# IN_OUT.net
KiCad netlist of a schematic drawn in Altium Designer
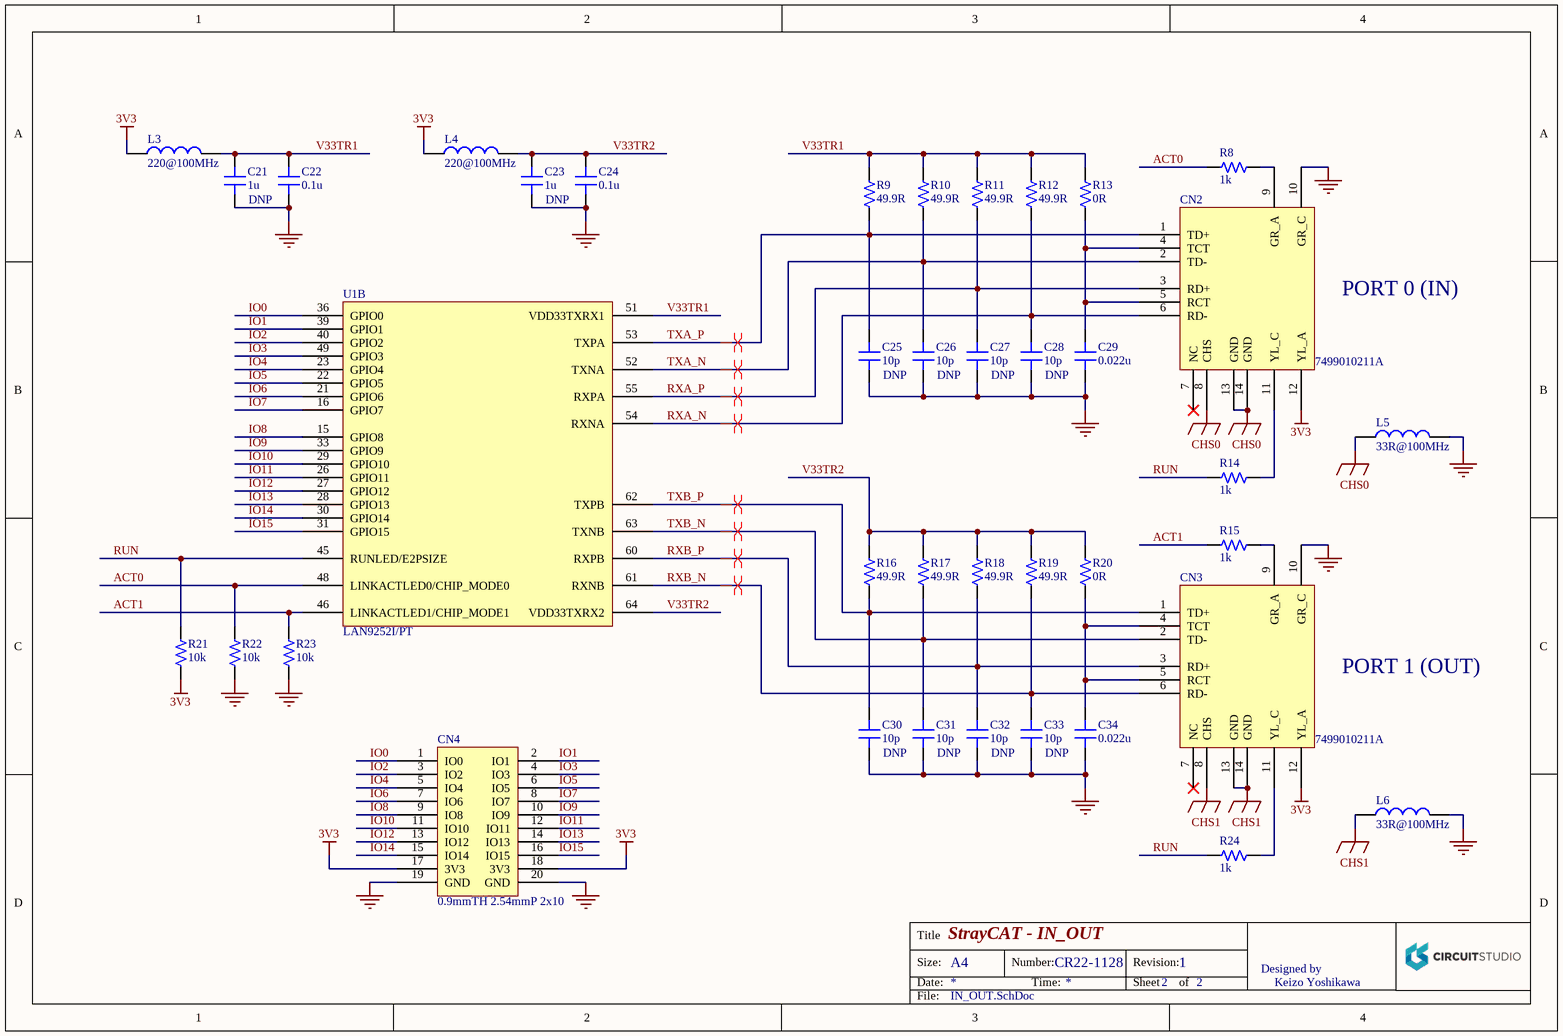
[diagram p0: IN_OUT.SchDoc]

(export (version "E")
  (design (tool "Eeschema 10.0.6"))
  (components
    (comp (ref "C21")
      (value "1u")
      (footprint "CGA3")
      (description "1608 1uF 25V X7R 10%")
      (libsource (lib "CGA3") (part "CGA3E1X7R1E105K080AC"))
    )
    (comp (ref "C22")
      (value "0.1u")
      (footprint "CGA3")
      (description "1608 0.1uF 50V X7R 10%")
      (libsource (lib "CGA3") (part "CGA3E2X7R1H104K080AA"))
    )
    (comp (ref "C23")
      (value "1u")
      (footprint "CGA3")
      (description "1608 1uF 25V X7R 10%")
      (libsource (lib "CGA3") (part "CGA3E1X7R1E105K080AC"))
    )
    (comp (ref "C24")
      (value "0.1u")
      (footprint "CGA3")
      (description "1608 0.1uF 50V X7R 10%")
      (libsource (lib "CGA3") (part "CGA3E2X7R1H104K080AA"))
    )
    (comp (ref "C25")
      (value "10p")
      (footprint "CGA3")
      (description "1608 10pF 50V C0G 5%")
      (libsource (lib "CGA3") (part "CGA3E2C0G1H100D080AA"))
    )
    (comp (ref "C26")
      (value "10p")
      (footprint "CGA3")
      (description "1608 10pF 50V C0G 5%")
      (libsource (lib "CGA3") (part "CGA3E2C0G1H100D080AA"))
    )
    (comp (ref "C27")
      (value "10p")
      (footprint "CGA3")
      (description "1608 10pF 50V C0G 5%")
      (libsource (lib "CGA3") (part "CGA3E2C0G1H100D080AA"))
    )
    (comp (ref "C28")
      (value "10p")
      (footprint "CGA3")
      (description "1608 10pF 50V C0G 5%")
      (libsource (lib "CGA3") (part "CGA3E2C0G1H100D080AA"))
    )
    (comp (ref "C29")
      (value "0.022u")
      (footprint "CGA3")
      (description "1608 0.022uF 50V X7R 10%")
      (libsource (lib "CGA3") (part "CGA3E2X7R1H223K080AA"))
    )
    (comp (ref "C30")
      (value "10p")
      (footprint "CGA3")
      (description "1608 10pF 50V C0G 5%")
      (libsource (lib "CGA3") (part "CGA3E2C0G1H100D080AA"))
    )
    (comp (ref "C31")
      (value "10p")
      (footprint "CGA3")
      (description "1608 10pF 50V C0G 5%")
      (libsource (lib "CGA3") (part "CGA3E2C0G1H100D080AA"))
    )
    (comp (ref "C32")
      (value "10p")
      (footprint "CGA3")
      (description "1608 10pF 50V C0G 5%")
      (libsource (lib "CGA3") (part "CGA3E2C0G1H100D080AA"))
    )
    (comp (ref "C33")
      (value "10p")
      (footprint "CGA3")
      (description "1608 10pF 50V C0G 5%")
      (libsource (lib "CGA3") (part "CGA3E2C0G1H100D080AA"))
    )
    (comp (ref "C34")
      (value "0.022u")
      (footprint "CGA3")
      (description "1608 0.022uF 50V X7R 10%")
      (libsource (lib "CGA3") (part "CGA3E2X7R1H223K080AA"))
    )
    (comp (ref "CN2")
      (value "7499010211A")
      (footprint "7499010211A")
      (description "WE-RJ45LAN 10/100 Base-T")
      (libsource (lib "7499010211A") (part "7499010211A"))
    )
    (comp (ref "CN3")
      (value "7499010211A")
      (footprint "7499010211A")
      (description "WE-RJ45LAN 10/100 Base-T")
      (libsource (lib "7499010211A") (part "7499010211A"))
    )
    (comp (ref "CN4")
      (value "0.9mmTH 2.54mmP 2x10")
      (footprint "61302021121")
      (description "WR-PHD Pin Header 20pin")
      (libsource (lib "61302021121") (part "61302021121"))
    )
    (comp (ref "L3")
      (value "220@100MHz")
      (footprint "BLM18EG221SN1D")
      (description "Noise Suppression Chip Ferrite Bead")
      (libsource (lib "BLM18EG221SN1D") (part "BLM18EG221SN1D"))
    )
    (comp (ref "L4")
      (value "220@100MHz")
      (footprint "BLM18EG221SN1D")
      (description "Noise Suppression Chip Ferrite Bead")
      (libsource (lib "BLM18EG221SN1D") (part "BLM18EG221SN1D"))
    )
    (comp (ref "L5")
      (value "33R@100MHz")
      (footprint "BLM18PG330SN1D")
      (description "Noise Suppression Chip Ferrite Bead")
      (libsource (lib "BLM18PG330SN1D") (part "BLM18PG330SN1D"))
    )
    (comp (ref "L6")
      (value "33R@100MHz")
      (footprint "BLM18PG330SN1D")
      (description "Noise Suppression Chip Ferrite Bead")
      (libsource (lib "BLM18PG330SN1D") (part "BLM18PG330SN1D"))
    )
    (comp (ref "R8")
      (value "1k")
      (footprint "RK73x1J")
      (description "1608 1kOhm 5% 1/8W")
      (libsource (lib "RK73X1J") (part "RK73B1JTTD102J"))
    )
    (comp (ref "R9")
      (value "49.9R")
      (footprint "RK73x1J")
      (description "1608 49.9Ohm 1% 1/8W")
      (libsource (lib "RK73X1J") (part "RK73H1JTTD49R9F"))
    )
    (comp (ref "R10")
      (value "49.9R")
      (footprint "RK73x1J")
      (description "1608 49.9Ohm 1% 1/8W")
      (libsource (lib "RK73X1J") (part "RK73H1JTTD49R9F"))
    )
    (comp (ref "R11")
      (value "49.9R")
      (footprint "RK73x1J")
      (description "1608 49.9Ohm 1% 1/8W")
      (libsource (lib "RK73X1J") (part "RK73H1JTTD49R9F"))
    )
    (comp (ref "R12")
      (value "49.9R")
      (footprint "RK73x1J")
      (description "1608 49.9Ohm 1% 1/8W")
      (libsource (lib "RK73X1J") (part "RK73H1JTTD49R9F"))
    )
    (comp (ref "R13")
      (value "0R")
      (footprint "RK73x1J")
      (description "1608 0-Ohm 1A")
      (libsource (lib "RK73X1J") (part "RK73Z1JTTD"))
    )
    (comp (ref "R14")
      (value "1k")
      (footprint "RK73x1J")
      (description "1608 1kOhm 5% 1/8W")
      (libsource (lib "RK73X1J") (part "RK73B1JTTD102J"))
    )
    (comp (ref "R15")
      (value "1k")
      (footprint "RK73x1J")
      (description "1608 1kOhm 5% 1/8W")
      (libsource (lib "RK73X1J") (part "RK73B1JTTD102J"))
    )
    (comp (ref "R16")
      (value "49.9R")
      (footprint "RK73x1J")
      (description "1608 49.9Ohm 1% 1/8W")
      (libsource (lib "RK73X1J") (part "RK73H1JTTD49R9F"))
    )
    (comp (ref "R17")
      (value "49.9R")
      (footprint "RK73x1J")
      (description "1608 49.9Ohm 1% 1/8W")
      (libsource (lib "RK73X1J") (part "RK73H1JTTD49R9F"))
    )
    (comp (ref "R18")
      (value "49.9R")
      (footprint "RK73x1J")
      (description "1608 49.9Ohm 1% 1/8W")
      (libsource (lib "RK73X1J") (part "RK73H1JTTD49R9F"))
    )
    (comp (ref "R19")
      (value "49.9R")
      (footprint "RK73x1J")
      (description "1608 49.9Ohm 1% 1/8W")
      (libsource (lib "RK73X1J") (part "RK73H1JTTD49R9F"))
    )
    (comp (ref "R20")
      (value "0R")
      (footprint "RK73x1J")
      (description "1608 0-Ohm 1A")
      (libsource (lib "RK73X1J") (part "RK73Z1JTTD"))
    )
    (comp (ref "R21")
      (value "10k")
      (footprint "RK73x1J")
      (description "1608 10kOhm 5% 1/10W")
      (libsource (lib "RK73X1J") (part "RK73B1JTTD103J"))
    )
    (comp (ref "R22")
      (value "10k")
      (footprint "RK73x1J")
      (description "1608 10kOhm 5% 1/10W")
      (libsource (lib "RK73X1J") (part "RK73B1JTTD103J"))
    )
    (comp (ref "R23")
      (value "10k")
      (footprint "RK73x1J")
      (description "1608 10kOhm 5% 1/10W")
      (libsource (lib "RK73X1J") (part "RK73B1JTTD103J"))
    )
    (comp (ref "R24")
      (value "1k")
      (footprint "RK73x1J")
      (description "1608 1kOhm 5% 1/8W")
      (libsource (lib "RK73X1J") (part "RK73B1JTTD102J"))
    )
    (comp (ref "U1")
      (value "LAN9252I/PT")
      (footprint "TSQFP50P1200X1200X105_HS-65N")
      (description "EtherCAT Slave Controller")
      (libsource (lib "LAN9252I_PT") (part "LAN9252I_PT"))
    )
  )
  (nets
    (net (code "1") (name "/ACT0") (class "Default")
      (node (ref "R22") (pin "1") (pinfunction "1_1") (pintype "passive"))
      (node (ref "R8") (pin "1") (pinfunction "1_1") (pintype "passive"))
      (node (ref "U1") (pin "48") (pinfunction "LINKACTLED0/CHIP_MODE0_48") (pintype "passive"))
    )
    (net (code "2") (name "/ACT1") (class "Default")
      (node (ref "R15") (pin "1") (pinfunction "1_1") (pintype "passive"))
      (node (ref "R23") (pin "1") (pinfunction "1_1") (pintype "passive"))
      (node (ref "U1") (pin "46") (pinfunction "LINKACTLED1/CHIP_MODE1_46") (pintype "passive"))
    )
    (net (code "3") (name "/IO0") (class "Default")
      (node (ref "CN4") (pin "1") (pinfunction "IO0_1") (pintype "passive"))
      (node (ref "U1") (pin "36") (pinfunction "GPIO0_36") (pintype "passive"))
    )
    (net (code "4") (name "/IO1") (class "Default")
      (node (ref "CN4") (pin "2") (pinfunction "IO1_2") (pintype "passive"))
      (node (ref "U1") (pin "39") (pinfunction "GPIO1_39") (pintype "passive"))
    )
    (net (code "5") (name "/IO2") (class "Default")
      (node (ref "CN4") (pin "3") (pinfunction "IO2_3") (pintype "passive"))
      (node (ref "U1") (pin "40") (pinfunction "GPIO2_40") (pintype "passive"))
    )
    (net (code "6") (name "/IO3") (class "Default")
      (node (ref "CN4") (pin "4") (pinfunction "IO3_4") (pintype "passive"))
      (node (ref "U1") (pin "49") (pinfunction "GPIO3_49") (pintype "passive"))
    )
    (net (code "7") (name "/IO4") (class "Default")
      (node (ref "CN4") (pin "5") (pinfunction "IO4_5") (pintype "passive"))
      (node (ref "U1") (pin "23") (pinfunction "GPIO4_23") (pintype "passive"))
    )
    (net (code "8") (name "/IO5") (class "Default")
      (node (ref "CN4") (pin "6") (pinfunction "IO5_6") (pintype "passive"))
      (node (ref "U1") (pin "22") (pinfunction "GPIO5_22") (pintype "passive"))
    )
    (net (code "9") (name "/IO6") (class "Default")
      (node (ref "CN4") (pin "7") (pinfunction "IO6_7") (pintype "passive"))
      (node (ref "U1") (pin "21") (pinfunction "GPIO6_21") (pintype "passive"))
    )
    (net (code "10") (name "/IO7") (class "Default")
      (node (ref "CN4") (pin "8") (pinfunction "IO7_8") (pintype "passive"))
      (node (ref "U1") (pin "16") (pinfunction "GPIO7_16") (pintype "passive"))
    )
    (net (code "11") (name "/IO8") (class "Default")
      (node (ref "CN4") (pin "9") (pinfunction "IO8_9") (pintype "passive"))
      (node (ref "U1") (pin "15") (pinfunction "GPIO8_15") (pintype "passive"))
    )
    (net (code "12") (name "/IO9") (class "Default")
      (node (ref "CN4") (pin "10") (pinfunction "IO9_10") (pintype "passive"))
      (node (ref "U1") (pin "33") (pinfunction "GPIO9_33") (pintype "passive"))
    )
    (net (code "13") (name "/IO10") (class "Default")
      (node (ref "CN4") (pin "11") (pinfunction "IO10_11") (pintype "passive"))
      (node (ref "U1") (pin "29") (pinfunction "GPIO10_29") (pintype "passive"))
    )
    (net (code "14") (name "/IO11") (class "Default")
      (node (ref "CN4") (pin "12") (pinfunction "IO11_12") (pintype "passive"))
      (node (ref "U1") (pin "26") (pinfunction "GPIO11_26") (pintype "passive"))
    )
    (net (code "15") (name "/IO12") (class "Default")
      (node (ref "CN4") (pin "13") (pinfunction "IO12_13") (pintype "passive"))
      (node (ref "U1") (pin "27") (pinfunction "GPIO12_27") (pintype "passive"))
    )
    (net (code "16") (name "/IO13") (class "Default")
      (node (ref "CN4") (pin "14") (pinfunction "IO13_14") (pintype "passive"))
      (node (ref "U1") (pin "28") (pinfunction "GPIO13_28") (pintype "passive"))
    )
    (net (code "17") (name "/IO14") (class "Default")
      (node (ref "CN4") (pin "15") (pinfunction "IO14_15") (pintype "passive"))
      (node (ref "U1") (pin "30") (pinfunction "GPIO14_30") (pintype "passive"))
    )
    (net (code "18") (name "/IO15") (class "Default")
      (node (ref "CN4") (pin "16") (pinfunction "IO15_16") (pintype "passive"))
      (node (ref "U1") (pin "31") (pinfunction "GPIO15_31") (pintype "passive"))
    )
    (net (code "19") (name "/RUN") (class "Default")
      (node (ref "R14") (pin "1") (pinfunction "1_1") (pintype "passive"))
      (node (ref "R21") (pin "1") (pinfunction "1_1") (pintype "passive"))
      (node (ref "R24") (pin "1") (pinfunction "1_1") (pintype "passive"))
      (node (ref "U1") (pin "45") (pinfunction "RUNLED/E2PSIZE_45") (pintype "passive"))
    )
    (net (code "20") (name "/RXA_N") (class "Default")
      (node (ref "C28") (pin "1") (pinfunction "1_1") (pintype "passive"))
      (node (ref "CN2") (pin "6") (pinfunction "RD-_6") (pintype "passive"))
      (node (ref "R12") (pin "2") (pinfunction "2_2") (pintype "passive"))
      (node (ref "U1") (pin "54") (pinfunction "RXNA_54") (pintype "passive"))
    )
    (net (code "21") (name "/RXA_P") (class "Default")
      (node (ref "C27") (pin "1") (pinfunction "1_1") (pintype "passive"))
      (node (ref "CN2") (pin "3") (pinfunction "RD+_3") (pintype "passive"))
      (node (ref "R11") (pin "2") (pinfunction "2_2") (pintype "passive"))
      (node (ref "U1") (pin "55") (pinfunction "RXPA_55") (pintype "passive"))
    )
    (net (code "22") (name "/RXB_N") (class "Default")
      (node (ref "C33") (pin "1") (pinfunction "1_1") (pintype "passive"))
      (node (ref "CN3") (pin "6") (pinfunction "RD-_6") (pintype "passive"))
      (node (ref "R19") (pin "2") (pinfunction "2_2") (pintype "passive"))
      (node (ref "U1") (pin "61") (pinfunction "RXNB_61") (pintype "passive"))
    )
    (net (code "23") (name "/RXB_P") (class "Default")
      (node (ref "C32") (pin "1") (pinfunction "1_1") (pintype "passive"))
      (node (ref "CN3") (pin "3") (pinfunction "RD+_3") (pintype "passive"))
      (node (ref "R18") (pin "2") (pinfunction "2_2") (pintype "passive"))
      (node (ref "U1") (pin "60") (pinfunction "RXPB_60") (pintype "passive"))
    )
    (net (code "24") (name "/TXA_N") (class "Default")
      (node (ref "C26") (pin "1") (pinfunction "1_1") (pintype "passive"))
      (node (ref "CN2") (pin "2") (pinfunction "TD-_2") (pintype "passive"))
      (node (ref "R10") (pin "2") (pinfunction "2_2") (pintype "passive"))
      (node (ref "U1") (pin "52") (pinfunction "TXNA_52") (pintype "passive"))
    )
    (net (code "25") (name "/TXA_P") (class "Default")
      (node (ref "C25") (pin "1") (pinfunction "1_1") (pintype "passive"))
      (node (ref "CN2") (pin "1") (pinfunction "TD+_1") (pintype "passive"))
      (node (ref "R9") (pin "2") (pinfunction "2_2") (pintype "passive"))
      (node (ref "U1") (pin "53") (pinfunction "TXPA_53") (pintype "passive"))
    )
    (net (code "26") (name "/TXB_N") (class "Default")
      (node (ref "C31") (pin "1") (pinfunction "1_1") (pintype "passive"))
      (node (ref "CN3") (pin "2") (pinfunction "TD-_2") (pintype "passive"))
      (node (ref "R17") (pin "2") (pinfunction "2_2") (pintype "passive"))
      (node (ref "U1") (pin "63") (pinfunction "TXNB_63") (pintype "passive"))
    )
    (net (code "27") (name "/TXB_P") (class "Default")
      (node (ref "C30") (pin "1") (pinfunction "1_1") (pintype "passive"))
      (node (ref "CN3") (pin "1") (pinfunction "TD+_1") (pintype "passive"))
      (node (ref "R16") (pin "2") (pinfunction "2_2") (pintype "passive"))
      (node (ref "U1") (pin "62") (pinfunction "TXPB_62") (pintype "passive"))
    )
    (net (code "28") (name "/V33TR1") (class "Default")
      (node (ref "C21") (pin "1") (pinfunction "1_1") (pintype "passive"))
      (node (ref "C22") (pin "1") (pinfunction "1_1") (pintype "passive"))
      (node (ref "L3") (pin "2") (pinfunction "2_2") (pintype "passive"))
      (node (ref "R10") (pin "1") (pinfunction "1_1") (pintype "passive"))
      (node (ref "R11") (pin "1") (pinfunction "1_1") (pintype "passive"))
      (node (ref "R12") (pin "1") (pinfunction "1_1") (pintype "passive"))
      (node (ref "R13") (pin "1") (pinfunction "1_1") (pintype "passive"))
      (node (ref "R9") (pin "1") (pinfunction "1_1") (pintype "passive"))
      (node (ref "U1") (pin "51") (pinfunction "VDD33TXRX1_51") (pintype "passive"))
    )
    (net (code "29") (name "/V33TR2") (class "Default")
      (node (ref "C23") (pin "1") (pinfunction "1_1") (pintype "passive"))
      (node (ref "C24") (pin "1") (pinfunction "1_1") (pintype "passive"))
      (node (ref "L4") (pin "2") (pinfunction "2_2") (pintype "passive"))
      (node (ref "R16") (pin "1") (pinfunction "1_1") (pintype "passive"))
      (node (ref "R17") (pin "1") (pinfunction "1_1") (pintype "passive"))
      (node (ref "R18") (pin "1") (pinfunction "1_1") (pintype "passive"))
      (node (ref "R19") (pin "1") (pinfunction "1_1") (pintype "passive"))
      (node (ref "R20") (pin "1") (pinfunction "1_1") (pintype "passive"))
      (node (ref "U1") (pin "64") (pinfunction "VDD33TXRX2_64") (pintype "passive"))
    )
    (net (code "30") (name "3V3") (class "Default")
      (node (ref "CN2") (pin "12") (pinfunction "YL_A_12") (pintype "passive"))
      (node (ref "CN3") (pin "12") (pinfunction "YL_A_12") (pintype "passive"))
      (node (ref "CN4") (pin "17") (pinfunction "3V3_17") (pintype "passive"))
      (node (ref "CN4") (pin "18") (pinfunction "3V3_18") (pintype "passive"))
      (node (ref "L3") (pin "1") (pinfunction "1_1") (pintype "passive"))
      (node (ref "L4") (pin "1") (pinfunction "1_1") (pintype "passive"))
      (node (ref "R21") (pin "2") (pinfunction "2_2") (pintype "passive"))
    )
    (net (code "31") (name "CHS0") (class "Default")
      (node (ref "CN2") (pin "13") (pinfunction "GND_13") (pintype "passive"))
      (node (ref "CN2") (pin "14") (pinfunction "GND_14") (pintype "passive"))
      (node (ref "CN2") (pin "8") (pinfunction "CHS_8") (pintype "passive"))
      (node (ref "L5") (pin "1") (pinfunction "1_1") (pintype "passive"))
    )
    (net (code "32") (name "CHS1") (class "Default")
      (node (ref "CN3") (pin "13") (pinfunction "GND_13") (pintype "passive"))
      (node (ref "CN3") (pin "14") (pinfunction "GND_14") (pintype "passive"))
      (node (ref "CN3") (pin "8") (pinfunction "CHS_8") (pintype "passive"))
      (node (ref "L6") (pin "1") (pinfunction "1_1") (pintype "passive"))
    )
    (net (code "33") (name "GND") (class "Default")
      (node (ref "C21") (pin "2") (pinfunction "2_2") (pintype "passive"))
      (node (ref "C22") (pin "2") (pinfunction "2_2") (pintype "passive"))
      (node (ref "C23") (pin "2") (pinfunction "2_2") (pintype "passive"))
      (node (ref "C24") (pin "2") (pinfunction "2_2") (pintype "passive"))
      (node (ref "C25") (pin "2") (pinfunction "2_2") (pintype "passive"))
      (node (ref "C26") (pin "2") (pinfunction "2_2") (pintype "passive"))
      (node (ref "C27") (pin "2") (pinfunction "2_2") (pintype "passive"))
      (node (ref "C28") (pin "2") (pinfunction "2_2") (pintype "passive"))
      (node (ref "C29") (pin "2") (pinfunction "2_2") (pintype "passive"))
      (node (ref "C30") (pin "2") (pinfunction "2_2") (pintype "passive"))
      (node (ref "C31") (pin "2") (pinfunction "2_2") (pintype "passive"))
      (node (ref "C32") (pin "2") (pinfunction "2_2") (pintype "passive"))
      (node (ref "C33") (pin "2") (pinfunction "2_2") (pintype "passive"))
      (node (ref "C34") (pin "2") (pinfunction "2_2") (pintype "passive"))
      (node (ref "CN2") (pin "10") (pinfunction "GR_C_10") (pintype "passive"))
      (node (ref "CN3") (pin "10") (pinfunction "GR_C_10") (pintype "passive"))
      (node (ref "CN4") (pin "19") (pinfunction "GND_19") (pintype "passive"))
      (node (ref "CN4") (pin "20") (pinfunction "GND_20") (pintype "passive"))
      (node (ref "L5") (pin "2") (pinfunction "2_2") (pintype "passive"))
      (node (ref "L6") (pin "2") (pinfunction "2_2") (pintype "passive"))
      (node (ref "R22") (pin "2") (pinfunction "2_2") (pintype "passive"))
      (node (ref "R23") (pin "2") (pinfunction "2_2") (pintype "passive"))
    )
    (net (code "34") (name "Net-(CN2-GR_A)") (class "Default")
      (node (ref "CN2") (pin "9") (pinfunction "GR_A_9") (pintype "passive"))
      (node (ref "R8") (pin "2") (pinfunction "2_2") (pintype "passive"))
    )
    (net (code "35") (name "Net-(CN2-RCT)") (class "Default")
      (node (ref "C29") (pin "1") (pinfunction "1_1") (pintype "passive"))
      (node (ref "CN2") (pin "4") (pinfunction "TCT_4") (pintype "passive"))
      (node (ref "CN2") (pin "5") (pinfunction "RCT_5") (pintype "passive"))
      (node (ref "R13") (pin "2") (pinfunction "2_2") (pintype "passive"))
    )
    (net (code "36") (name "Net-(CN2-YL_C)") (class "Default")
      (node (ref "CN2") (pin "11") (pinfunction "YL_C_11") (pintype "passive"))
      (node (ref "R14") (pin "2") (pinfunction "2_2") (pintype "passive"))
    )
    (net (code "37") (name "Net-(CN3-GR_A)") (class "Default")
      (node (ref "CN3") (pin "9") (pinfunction "GR_A_9") (pintype "passive"))
      (node (ref "R15") (pin "2") (pinfunction "2_2") (pintype "passive"))
    )
    (net (code "38") (name "Net-(CN3-RCT)") (class "Default")
      (node (ref "C34") (pin "1") (pinfunction "1_1") (pintype "passive"))
      (node (ref "CN3") (pin "4") (pinfunction "TCT_4") (pintype "passive"))
      (node (ref "CN3") (pin "5") (pinfunction "RCT_5") (pintype "passive"))
      (node (ref "R20") (pin "2") (pinfunction "2_2") (pintype "passive"))
    )
    (net (code "39") (name "Net-(CN3-YL_C)") (class "Default")
      (node (ref "CN3") (pin "11") (pinfunction "YL_C_11") (pintype "passive"))
      (node (ref "R24") (pin "2") (pinfunction "2_2") (pintype "passive"))
    )
    (net (code "40") (name "unconnected-(CN2-NC-Pad7)") (class "Default")
      (node (ref "CN2") (pin "7") (pinfunction "NC_7") (pintype "passive+no_connect"))
    )
    (net (code "41") (name "unconnected-(CN3-NC-Pad7)") (class "Default")
      (node (ref "CN3") (pin "7") (pinfunction "NC_7") (pintype "passive+no_connect"))
    )
  )
)
